# LVDS2RGB_DS90C384A.net
KiCad netlist of a schematic drawn in Altium Designer
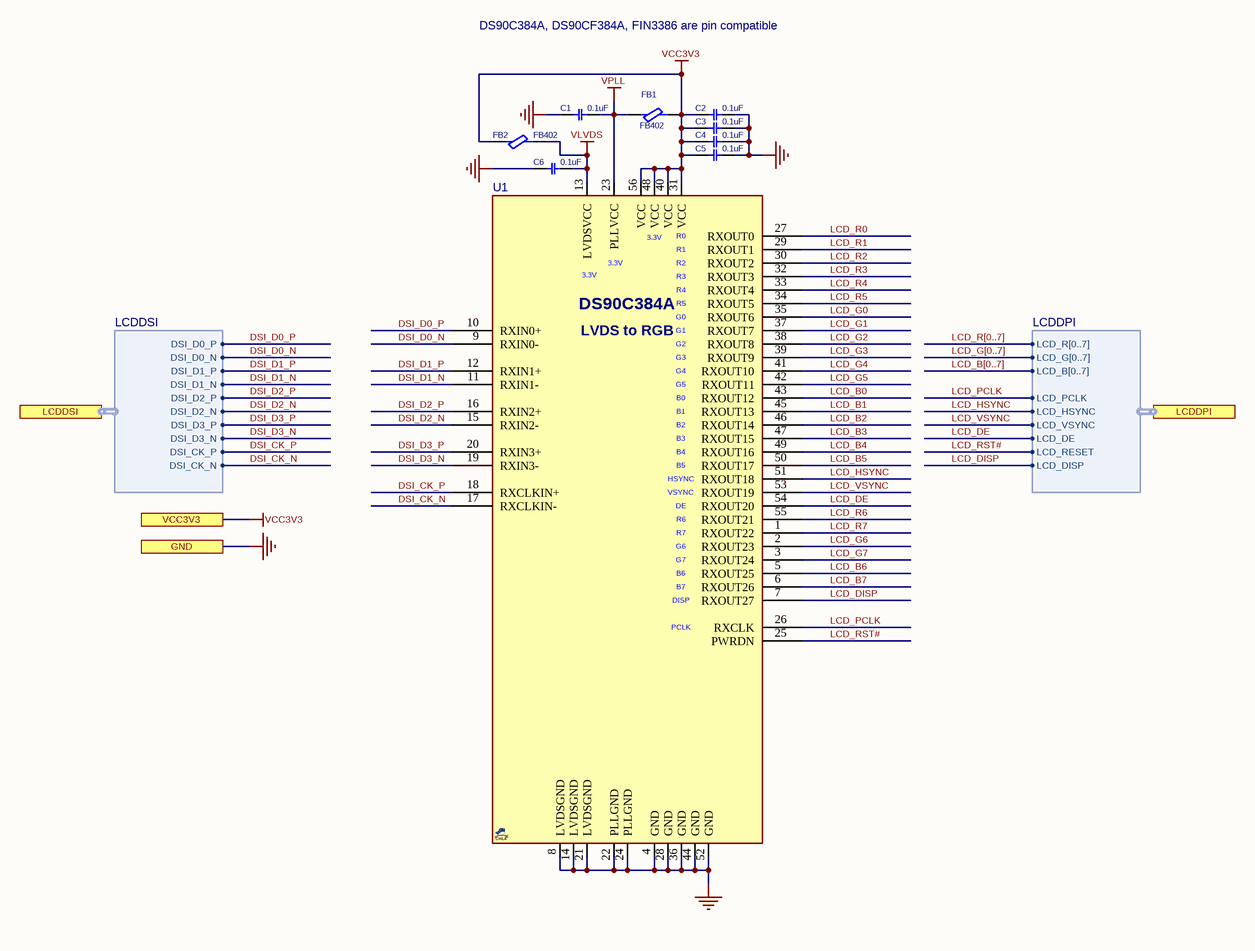
[diagram p0: LVDS2RGB_DS90C384A.SchDoc]

(export (version "E")
  (design (tool "Eeschema 10.0.6"))
  (components
    (comp (ref "C1")
      (value "0.1uF")
      (footprint "C0402")
      (description "CAP, MLCC")
      (fields (field (name "MANF_P#") "GRM155R71H104KE14D") (field (name "MANF") "Murata"))
      (libsource (lib "passive_smd") (part "CAP_SMD_MLCC"))
    )
    (comp (ref "C2")
      (value "0.1uF")
      (footprint "C0402")
      (description "CAP, MLCC")
      (fields (field (name "MANF_P#") "GRM155R71H104KE14D") (field (name "MANF") "Murata"))
      (libsource (lib "passive_smd") (part "CAP_SMD_MLCC"))
    )
    (comp (ref "C3")
      (value "0.1uF")
      (footprint "C0402")
      (description "CAP, MLCC")
      (fields (field (name "MANF_P#") "GRM155R71H104KE14D") (field (name "MANF") "Murata"))
      (libsource (lib "passive_smd") (part "CAP_SMD_MLCC"))
    )
    (comp (ref "C4")
      (value "0.1uF")
      (footprint "C0402")
      (description "CAP, MLCC")
      (fields (field (name "MANF_P#") "GRM155R71H104KE14D") (field (name "MANF") "Murata"))
      (libsource (lib "passive_smd") (part "CAP_SMD_MLCC"))
    )
    (comp (ref "C5")
      (value "0.1uF")
      (footprint "C0402")
      (description "CAP, MLCC")
      (fields (field (name "MANF_P#") "GRM155R71H104KE14D") (field (name "MANF") "Murata"))
      (libsource (lib "passive_smd") (part "CAP_SMD_MLCC"))
    )
    (comp (ref "C6")
      (value "0.1uF")
      (footprint "C0402")
      (description "CAP, MLCC")
      (fields (field (name "MANF_P#") "GRM155R71H104KE14D") (field (name "MANF") "Murata"))
      (libsource (lib "passive_smd") (part "CAP_SMD_MLCC"))
    )
    (comp (ref "FB1")
      (value "FB402")
      (footprint "L0402")
      (description "FERRITE_Bead, 0402, 0.5A, 200mOhm, 120@100MHz")
      (fields (field (name "MANF") "MURATA") (field (name "MANF_P#") "BLM15AG121SN1D"))
      (libsource (lib "emi_filter") (part "FBEAD_SMD_BLM15PD121"))
    )
    (comp (ref "FB2")
      (value "FB402")
      (footprint "L0402")
      (description "FERRITE_Bead, 0402, 0.5A, 200mOhm, 120@100MHz")
      (fields (field (name "MANF") "MURATA") (field (name "MANF_P#") "BLM15AG121SN1D"))
      (libsource (lib "emi_filter") (part "FBEAD_SMD_BLM15PD121"))
    )
    (comp (ref "U1")
      (value "DS90C384A")
      (footprint "SOG50_56")
      (description "LVDS receiver, RGB transmitter")
      (fields (field (name "MANF") "Texas Instruments") (field (name "MANF_P#") "DS90C384AMT"))
      (libsource (lib "display_interface_bridge") (part "DS90C384A_TSSOP56"))
    )
  )
  (nets
    (net (code "3") (name "/DSI_CK_N") (class "Default")
      (node (ref "U1") (pin "17") (pinfunction "RXCLKIN-_17") (pintype "passive"))
    )
    (net (code "4") (name "/DSI_CK_P") (class "Default")
      (node (ref "U1") (pin "18") (pinfunction "RXCLKIN+_18") (pintype "passive"))
    )
    (net (code "5") (name "/DSI_D0_N") (class "Default")
      (node (ref "U1") (pin "9") (pinfunction "RXIN0-_9") (pintype "passive"))
    )
    (net (code "6") (name "/DSI_D0_P") (class "Default")
      (node (ref "U1") (pin "10") (pinfunction "RXIN0+_10") (pintype "passive"))
    )
    (net (code "7") (name "/DSI_D1_N") (class "Default")
      (node (ref "U1") (pin "11") (pinfunction "RXIN1-_11") (pintype "passive"))
    )
    (net (code "8") (name "/DSI_D1_P") (class "Default")
      (node (ref "U1") (pin "12") (pinfunction "RXIN1+_12") (pintype "passive"))
    )
    (net (code "9") (name "/DSI_D2_N") (class "Default")
      (node (ref "U1") (pin "15") (pinfunction "RXIN2-_15") (pintype "passive"))
    )
    (net (code "10") (name "/DSI_D2_P") (class "Default")
      (node (ref "U1") (pin "16") (pinfunction "RXIN2+_16") (pintype "passive"))
    )
    (net (code "11") (name "/DSI_D3_N") (class "Default")
      (node (ref "U1") (pin "19") (pinfunction "RXIN3-_19") (pintype "passive"))
    )
    (net (code "12") (name "/DSI_D3_P") (class "Default")
      (node (ref "U1") (pin "20") (pinfunction "RXIN3+_20") (pintype "passive"))
    )
    (net (code "14") (name "/LCD_B0") (class "Default")
      (node (ref "U1") (pin "43") (pinfunction "RXOUT12_43") (pintype "passive"))
    )
    (net (code "15") (name "/LCD_B1") (class "Default")
      (node (ref "U1") (pin "45") (pinfunction "RXOUT13_45") (pintype "passive"))
    )
    (net (code "16") (name "/LCD_B2") (class "Default")
      (node (ref "U1") (pin "46") (pinfunction "RXOUT14_46") (pintype "passive"))
    )
    (net (code "17") (name "/LCD_B3") (class "Default")
      (node (ref "U1") (pin "47") (pinfunction "RXOUT15_47") (pintype "passive"))
    )
    (net (code "18") (name "/LCD_B4") (class "Default")
      (node (ref "U1") (pin "49") (pinfunction "RXOUT16_49") (pintype "passive"))
    )
    (net (code "19") (name "/LCD_B5") (class "Default")
      (node (ref "U1") (pin "50") (pinfunction "RXOUT17_50") (pintype "passive"))
    )
    (net (code "20") (name "/LCD_B6") (class "Default")
      (node (ref "U1") (pin "5") (pinfunction "RXOUT25_5") (pintype "passive"))
    )
    (net (code "21") (name "/LCD_B7") (class "Default")
      (node (ref "U1") (pin "6") (pinfunction "RXOUT26_6") (pintype "passive"))
    )
    (net (code "22") (name "/LCD_DE") (class "Default")
      (node (ref "U1") (pin "54") (pinfunction "RXOUT20_54") (pintype "passive"))
    )
    (net (code "23") (name "/LCD_DISP") (class "Default")
      (node (ref "U1") (pin "7") (pinfunction "RXOUT27_7") (pintype "passive"))
    )
    (net (code "24") (name "/LCD_G0") (class "Default")
      (node (ref "U1") (pin "35") (pinfunction "RXOUT6_35") (pintype "passive"))
    )
    (net (code "25") (name "/LCD_G1") (class "Default")
      (node (ref "U1") (pin "37") (pinfunction "RXOUT7_37") (pintype "passive"))
    )
    (net (code "26") (name "/LCD_G2") (class "Default")
      (node (ref "U1") (pin "38") (pinfunction "RXOUT8_38") (pintype "passive"))
    )
    (net (code "27") (name "/LCD_G3") (class "Default")
      (node (ref "U1") (pin "39") (pinfunction "RXOUT9_39") (pintype "passive"))
    )
    (net (code "28") (name "/LCD_G4") (class "Default")
      (node (ref "U1") (pin "41") (pinfunction "RXOUT10_41") (pintype "passive"))
    )
    (net (code "29") (name "/LCD_G5") (class "Default")
      (node (ref "U1") (pin "42") (pinfunction "RXOUT11_42") (pintype "passive"))
    )
    (net (code "30") (name "/LCD_G6") (class "Default")
      (node (ref "U1") (pin "2") (pinfunction "RXOUT23_2") (pintype "passive"))
    )
    (net (code "31") (name "/LCD_G7") (class "Default")
      (node (ref "U1") (pin "3") (pinfunction "RXOUT24_3") (pintype "passive"))
    )
    (net (code "33") (name "/LCD_HSYNC") (class "Default")
      (node (ref "U1") (pin "51") (pinfunction "RXOUT18_51") (pintype "passive"))
    )
    (net (code "34") (name "/LCD_PCLK") (class "Default")
      (node (ref "U1") (pin "26") (pinfunction "RXCLK_26") (pintype "passive"))
    )
    (net (code "35") (name "/LCD_R0") (class "Default")
      (node (ref "U1") (pin "27") (pinfunction "RXOUT0_27") (pintype "passive"))
    )
    (net (code "36") (name "/LCD_R1") (class "Default")
      (node (ref "U1") (pin "29") (pinfunction "RXOUT1_29") (pintype "passive"))
    )
    (net (code "37") (name "/LCD_R2") (class "Default")
      (node (ref "U1") (pin "30") (pinfunction "RXOUT2_30") (pintype "passive"))
    )
    (net (code "38") (name "/LCD_R3") (class "Default")
      (node (ref "U1") (pin "32") (pinfunction "RXOUT3_32") (pintype "passive"))
    )
    (net (code "39") (name "/LCD_R4") (class "Default")
      (node (ref "U1") (pin "33") (pinfunction "RXOUT4_33") (pintype "passive"))
    )
    (net (code "40") (name "/LCD_R5") (class "Default")
      (node (ref "U1") (pin "34") (pinfunction "RXOUT5_34") (pintype "passive"))
    )
    (net (code "41") (name "/LCD_R6") (class "Default")
      (node (ref "U1") (pin "55") (pinfunction "RXOUT21_55") (pintype "passive"))
    )
    (net (code "42") (name "/LCD_R7") (class "Default")
      (node (ref "U1") (pin "1") (pinfunction "RXOUT22_1") (pintype "passive"))
    )
    (net (code "43") (name "/LCD_RST#") (class "Default")
      (node (ref "U1") (pin "25") (pinfunction "PWRDN_25") (pintype "passive"))
    )
    (net (code "45") (name "/LCD_VSYNC") (class "Default")
      (node (ref "U1") (pin "53") (pinfunction "RXOUT19_53") (pintype "passive"))
    )
    (net (code "48") (name "GND") (class "Default")
      (node (ref "C1") (pin "2") (pinfunction "2_2") (pintype "passive"))
      (node (ref "C2") (pin "1") (pinfunction "1_1") (pintype "passive"))
      (node (ref "C3") (pin "1") (pinfunction "1_1") (pintype "passive"))
      (node (ref "C4") (pin "1") (pinfunction "1_1") (pintype "passive"))
      (node (ref "C5") (pin "1") (pinfunction "1_1") (pintype "passive"))
      (node (ref "C6") (pin "2") (pinfunction "2_2") (pintype "passive"))
      (node (ref "U1") (pin "14") (pinfunction "LVDSGND_14") (pintype "passive"))
      (node (ref "U1") (pin "21") (pinfunction "LVDSGND_21") (pintype "passive"))
      (node (ref "U1") (pin "22") (pinfunction "PLLGND_22") (pintype "passive"))
      (node (ref "U1") (pin "24") (pinfunction "PLLGND_24") (pintype "passive"))
      (node (ref "U1") (pin "28") (pinfunction "GND_28") (pintype "passive"))
      (node (ref "U1") (pin "36") (pinfunction "GND_36") (pintype "passive"))
      (node (ref "U1") (pin "4") (pinfunction "GND_4") (pintype "passive"))
      (node (ref "U1") (pin "44") (pinfunction "GND_44") (pintype "passive"))
      (node (ref "U1") (pin "52") (pinfunction "GND_52") (pintype "passive"))
      (node (ref "U1") (pin "8") (pinfunction "LVDSGND_8") (pintype "passive"))
    )
    (net (code "49") (name "VCC3V3") (class "Default")
      (node (ref "C2") (pin "2") (pinfunction "2_2") (pintype "passive"))
      (node (ref "C3") (pin "2") (pinfunction "2_2") (pintype "passive"))
      (node (ref "C4") (pin "2") (pinfunction "2_2") (pintype "passive"))
      (node (ref "C5") (pin "2") (pinfunction "2_2") (pintype "passive"))
      (node (ref "FB1") (pin "2") (pinfunction "2_2") (pintype "passive"))
      (node (ref "FB2") (pin "1") (pinfunction "1_1") (pintype "passive"))
      (node (ref "U1") (pin "31") (pinfunction "VCC_31") (pintype "passive"))
      (node (ref "U1") (pin "40") (pinfunction "VCC_40") (pintype "passive"))
      (node (ref "U1") (pin "48") (pinfunction "VCC_48") (pintype "passive"))
      (node (ref "U1") (pin "56") (pinfunction "VCC_56") (pintype "passive"))
    )
    (net (code "50") (name "VLVDS") (class "Default")
      (node (ref "C6") (pin "1") (pinfunction "1_1") (pintype "passive"))
      (node (ref "FB2") (pin "2") (pinfunction "2_2") (pintype "passive"))
      (node (ref "U1") (pin "13") (pinfunction "LVDSVCC_13") (pintype "passive"))
    )
    (net (code "51") (name "VPLL") (class "Default")
      (node (ref "C1") (pin "1") (pinfunction "1_1") (pintype "passive"))
      (node (ref "FB1") (pin "1") (pinfunction "1_1") (pintype "passive"))
      (node (ref "U1") (pin "23") (pinfunction "PLLVCC_23") (pintype "passive"))
    )
  )
)
